# rgb_test_board_1.net
KiCad netlist of a schematic drawn in EAGLE
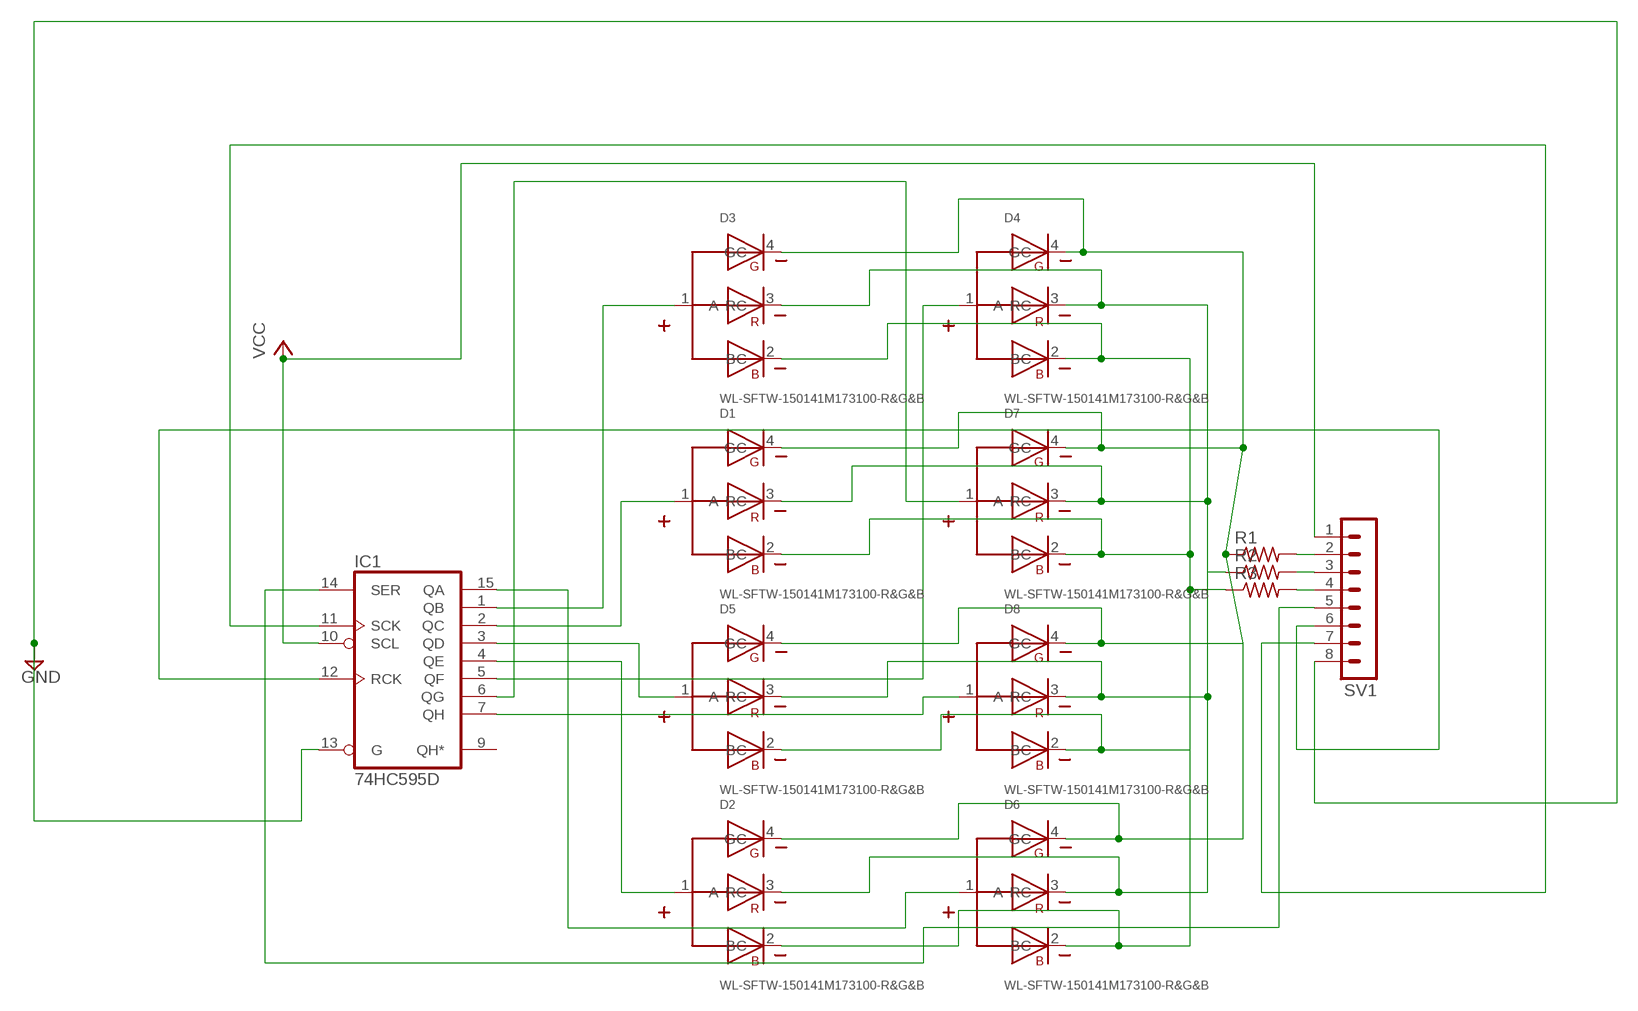
[diagram p0: schematic, sheet 1]

(export (version "E")
  (design (tool "Eeschema 10.0.6"))
  (components
    (comp (ref "D1")
      (value "WL-SFTW-150141M173100-R&G&B")
      (footprint "eagle-import:3528-COMMON-ANODE")
      (libsource (lib "eagle-import") (part "WL-SFTW-150141M173100-R&G&B"))
    )
    (comp (ref "D2")
      (value "WL-SFTW-150141M173100-R&G&B")
      (footprint "eagle-import:3528-COMMON-ANODE")
      (libsource (lib "eagle-import") (part "WL-SFTW-150141M173100-R&G&B"))
    )
    (comp (ref "D3")
      (value "WL-SFTW-150141M173100-R&G&B")
      (footprint "eagle-import:3528-COMMON-ANODE")
      (libsource (lib "eagle-import") (part "WL-SFTW-150141M173100-R&G&B"))
    )
    (comp (ref "D4")
      (value "WL-SFTW-150141M173100-R&G&B")
      (footprint "eagle-import:3528-COMMON-ANODE")
      (libsource (lib "eagle-import") (part "WL-SFTW-150141M173100-R&G&B"))
    )
    (comp (ref "D5")
      (value "WL-SFTW-150141M173100-R&G&B")
      (footprint "eagle-import:3528-COMMON-ANODE")
      (libsource (lib "eagle-import") (part "WL-SFTW-150141M173100-R&G&B"))
    )
    (comp (ref "D6")
      (value "WL-SFTW-150141M173100-R&G&B")
      (footprint "eagle-import:3528-COMMON-ANODE")
      (libsource (lib "eagle-import") (part "WL-SFTW-150141M173100-R&G&B"))
    )
    (comp (ref "D7")
      (value "WL-SFTW-150141M173100-R&G&B")
      (footprint "eagle-import:3528-COMMON-ANODE")
      (libsource (lib "eagle-import") (part "WL-SFTW-150141M173100-R&G&B"))
    )
    (comp (ref "D8")
      (value "WL-SFTW-150141M173100-R&G&B")
      (footprint "eagle-import:3528-COMMON-ANODE")
      (libsource (lib "eagle-import") (part "WL-SFTW-150141M173100-R&G&B"))
    )
    (comp (ref "IC1")
      (value "74HC595D")
      (footprint "eagle-import:SO16")
      (libsource (lib "eagle-import") (part "74595DHC"))
    )
    (comp (ref "R1")
      (value "R-US_R0805")
      (footprint "eagle-import:R0805")
      (libsource (lib "eagle-import") (part "R-US_R0805"))
    )
    (comp (ref "R2")
      (value "R-US_R0805")
      (footprint "eagle-import:R0805")
      (libsource (lib "eagle-import") (part "R-US_R0805"))
    )
    (comp (ref "R3")
      (value "R-US_R0805")
      (footprint "eagle-import:R0805")
      (libsource (lib "eagle-import") (part "R-US_R0805"))
    )
    (comp (ref "SV1")
      (value "MA08-1")
      (footprint "eagle-import:MA08-1")
      (libsource (lib "eagle-import") (part "MA08-1"))
    )
  )
  (nets
    (net (code "1") (name "GND") (class "Default")
      (node (ref "IC1") (pin "13") (pinfunction "G_13") (pintype "input"))
      (node (ref "SV1") (pin "8") (pinfunction "8_8") (pintype "passive"))
    )
    (net (code "2") (name "Net-(D1-A)") (class "Default")
      (node (ref "D1") (pin "1") (pinfunction "A_1") (pintype "bidirectional"))
      (node (ref "IC1") (pin "2") (pinfunction "QC_2") (pintype "tri_state"))
    )
    (net (code "3") (name "Net-(D1-BC)") (class "Default")
      (node (ref "D1") (pin "2") (pinfunction "BC_2") (pintype "bidirectional"))
      (node (ref "D2") (pin "2") (pinfunction "BC_2") (pintype "bidirectional"))
      (node (ref "D3") (pin "2") (pinfunction "BC_2") (pintype "bidirectional"))
      (node (ref "D4") (pin "2") (pinfunction "BC_2") (pintype "bidirectional"))
      (node (ref "D5") (pin "2") (pinfunction "BC_2") (pintype "bidirectional"))
      (node (ref "D6") (pin "2") (pinfunction "BC_2") (pintype "bidirectional"))
      (node (ref "D7") (pin "2") (pinfunction "BC_2") (pintype "bidirectional"))
      (node (ref "D8") (pin "2") (pinfunction "BC_2") (pintype "bidirectional"))
      (node (ref "R3") (pin "1") (pinfunction "1_1") (pintype "passive"))
    )
    (net (code "4") (name "Net-(D1-GC)") (class "Default")
      (node (ref "D1") (pin "4") (pinfunction "GC_4") (pintype "bidirectional"))
      (node (ref "D2") (pin "4") (pinfunction "GC_4") (pintype "bidirectional"))
      (node (ref "D3") (pin "4") (pinfunction "GC_4") (pintype "bidirectional"))
      (node (ref "D4") (pin "4") (pinfunction "GC_4") (pintype "bidirectional"))
      (node (ref "D5") (pin "4") (pinfunction "GC_4") (pintype "bidirectional"))
      (node (ref "D6") (pin "4") (pinfunction "GC_4") (pintype "bidirectional"))
      (node (ref "D7") (pin "4") (pinfunction "GC_4") (pintype "bidirectional"))
      (node (ref "D8") (pin "4") (pinfunction "GC_4") (pintype "bidirectional"))
      (node (ref "R1") (pin "1") (pinfunction "1_1") (pintype "passive"))
    )
    (net (code "5") (name "Net-(D1-RC)") (class "Default")
      (node (ref "D1") (pin "3") (pinfunction "RC_3") (pintype "bidirectional"))
      (node (ref "D2") (pin "3") (pinfunction "RC_3") (pintype "bidirectional"))
      (node (ref "D3") (pin "3") (pinfunction "RC_3") (pintype "bidirectional"))
      (node (ref "D4") (pin "3") (pinfunction "RC_3") (pintype "bidirectional"))
      (node (ref "D5") (pin "3") (pinfunction "RC_3") (pintype "bidirectional"))
      (node (ref "D6") (pin "3") (pinfunction "RC_3") (pintype "bidirectional"))
      (node (ref "D7") (pin "3") (pinfunction "RC_3") (pintype "bidirectional"))
      (node (ref "D8") (pin "3") (pinfunction "RC_3") (pintype "bidirectional"))
      (node (ref "R2") (pin "1") (pinfunction "1_1") (pintype "passive"))
    )
    (net (code "6") (name "Net-(D2-A)") (class "Default")
      (node (ref "D2") (pin "1") (pinfunction "A_1") (pintype "bidirectional"))
      (node (ref "IC1") (pin "4") (pinfunction "QE_4") (pintype "tri_state"))
    )
    (net (code "7") (name "Net-(D3-A)") (class "Default")
      (node (ref "D3") (pin "1") (pinfunction "A_1") (pintype "bidirectional"))
      (node (ref "IC1") (pin "1") (pinfunction "QB_1") (pintype "tri_state"))
    )
    (net (code "8") (name "Net-(D4-A)") (class "Default")
      (node (ref "D4") (pin "1") (pinfunction "A_1") (pintype "bidirectional"))
      (node (ref "IC1") (pin "5") (pinfunction "QF_5") (pintype "tri_state"))
    )
    (net (code "9") (name "Net-(D5-A)") (class "Default")
      (node (ref "D5") (pin "1") (pinfunction "A_1") (pintype "bidirectional"))
      (node (ref "IC1") (pin "3") (pinfunction "QD_3") (pintype "tri_state"))
    )
    (net (code "10") (name "Net-(D6-A)") (class "Default")
      (node (ref "D6") (pin "1") (pinfunction "A_1") (pintype "bidirectional"))
      (node (ref "IC1") (pin "15") (pinfunction "QA_15") (pintype "tri_state"))
    )
    (net (code "11") (name "Net-(D7-A)") (class "Default")
      (node (ref "D7") (pin "1") (pinfunction "A_1") (pintype "bidirectional"))
      (node (ref "IC1") (pin "6") (pinfunction "QG_6") (pintype "tri_state"))
    )
    (net (code "12") (name "Net-(D8-A)") (class "Default")
      (node (ref "D8") (pin "1") (pinfunction "A_1") (pintype "bidirectional"))
      (node (ref "IC1") (pin "7") (pinfunction "QH_7") (pintype "tri_state"))
    )
    (net (code "13") (name "Net-(IC1A-RCK)") (class "Default")
      (node (ref "IC1") (pin "12") (pinfunction "RCK_12") (pintype "input"))
      (node (ref "SV1") (pin "6") (pinfunction "6_6") (pintype "passive"))
    )
    (net (code "14") (name "Net-(IC1A-SCK)") (class "Default")
      (node (ref "IC1") (pin "11") (pinfunction "SCK_11") (pintype "input"))
      (node (ref "SV1") (pin "7") (pinfunction "7_7") (pintype "passive"))
    )
    (net (code "15") (name "Net-(IC1A-SER)") (class "Default")
      (node (ref "IC1") (pin "14") (pinfunction "SER_14") (pintype "input"))
      (node (ref "SV1") (pin "5") (pinfunction "5_5") (pintype "passive"))
    )
    (net (code "16") (name "Net-(R1-Pad2)") (class "Default")
      (node (ref "R1") (pin "2") (pinfunction "2_2") (pintype "passive"))
      (node (ref "SV1") (pin "2") (pinfunction "2_2") (pintype "passive"))
    )
    (net (code "17") (name "Net-(R2-Pad2)") (class "Default")
      (node (ref "R2") (pin "2") (pinfunction "2_2") (pintype "passive"))
      (node (ref "SV1") (pin "3") (pinfunction "3_3") (pintype "passive"))
    )
    (net (code "18") (name "Net-(R3-Pad2)") (class "Default")
      (node (ref "R3") (pin "2") (pinfunction "2_2") (pintype "passive"))
      (node (ref "SV1") (pin "4") (pinfunction "4_4") (pintype "passive"))
    )
    (net (code "19") (name "VCC") (class "Default")
      (node (ref "IC1") (pin "10") (pinfunction "SCL_10") (pintype "input"))
      (node (ref "SV1") (pin "1") (pinfunction "1_1") (pintype "passive"))
    )
    (net (code "20") (name "unconnected-(IC1A-QH*-Pad9)") (class "Default")
      (node (ref "IC1") (pin "9") (pinfunction "QH*_9") (pintype "tri_state"))
    )
  )
)
